# PowerSupply.net
KiCad netlist of a schematic drawn in Altium Designer
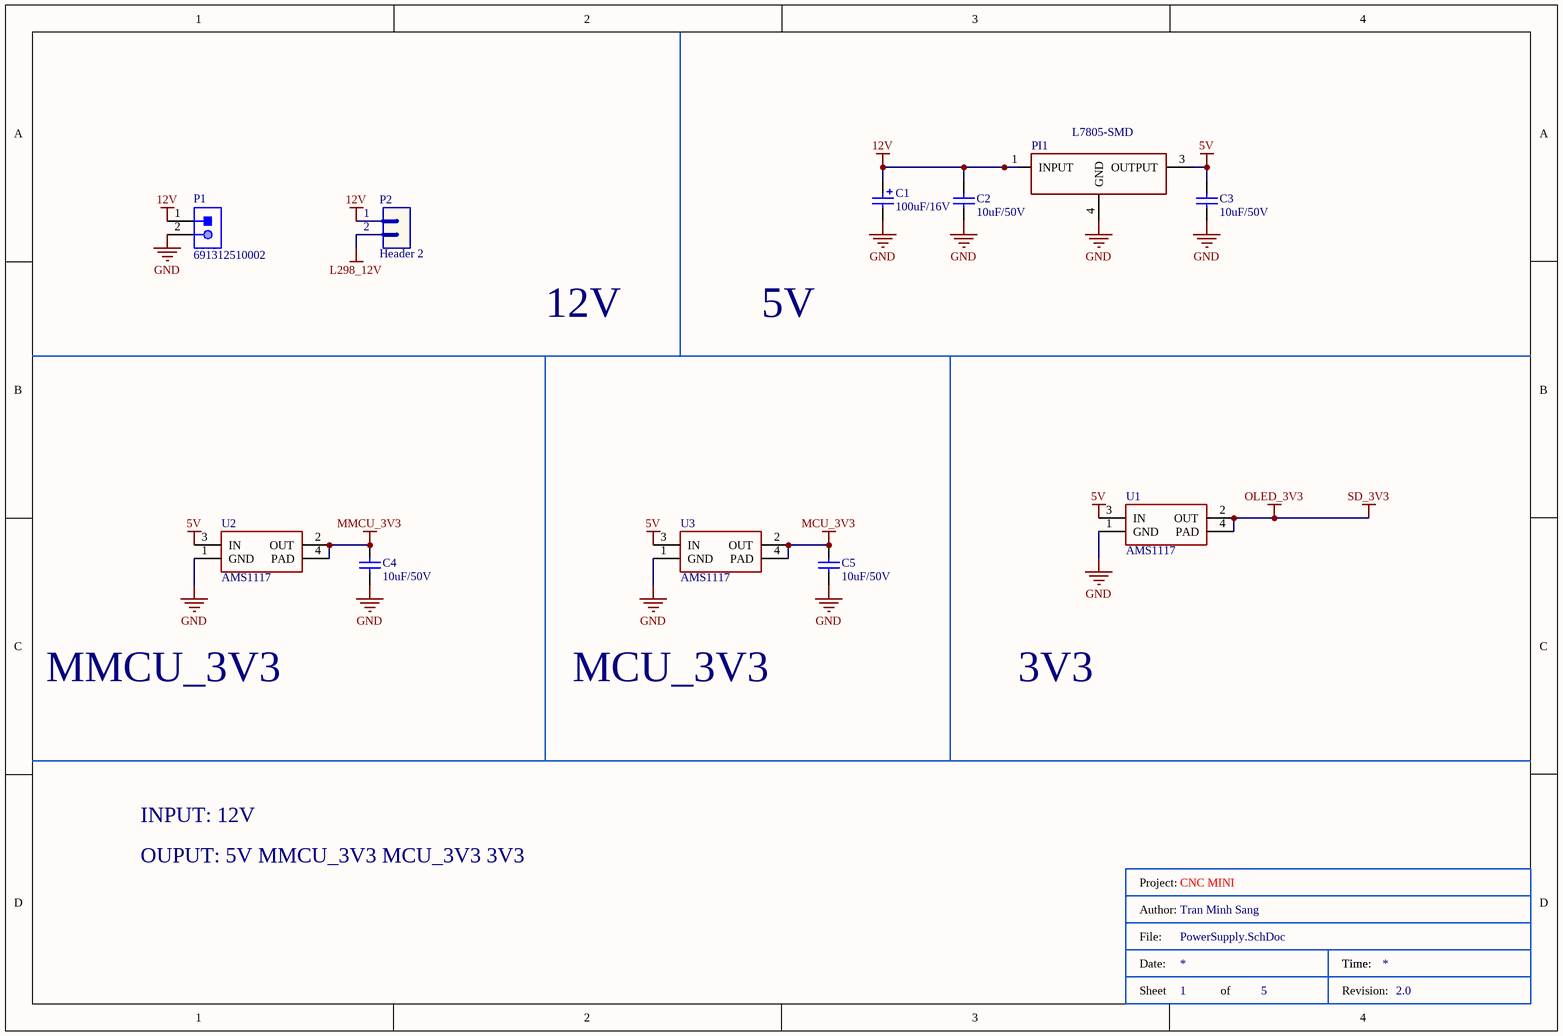
[diagram p0: PowerSupply.SchDoc]

(export (version "E")
  (design (tool "Eeschema 10.0.6"))
  (components
    (comp (ref "C1")
      (value "100uF/16V")
      (footprint "CAP-SM-AL-SIZE-D-D6L6")
      (description "CAP ALUM 100UF 20% 16V SMD")
      (fields
        (field (name "MANUFACTURER") "Nichicon")
        (field (name "MANUFACTURER PART NUMBER") "UWX1C101MCL1GB")
      )
      (libsource (lib "capacitor-smd") (part "Cap-Al-100uF-16V-D6L5"))
    )
    (comp (ref "C2")
      (value "10uF/50V")
      (footprint "CAP-SM-0805")
      (description "CAP CER 10UF 50V X5R 0805")
      (fields
        (field (name "MANUFACTURER") "Yageo")
        (field (name "MANUFACTURER PART NUMBER") "CC0805KKX5R9BB106")
      )
      (libsource (lib "capacitor-smd") (part "Cap-10uF-50V-0805"))
    )
    (comp (ref "C3")
      (value "10uF/50V")
      (footprint "CAP-SM-0805")
      (description "CAP CER 10UF 50V X5R 0805")
      (fields
        (field (name "MANUFACTURER") "Yageo")
        (field (name "MANUFACTURER PART NUMBER") "CC0805KKX5R9BB106")
      )
      (libsource (lib "capacitor-smd") (part "Cap-10uF-50V-0805"))
    )
    (comp (ref "C4")
      (value "10uF/50V")
      (footprint "CAP-SM-0805")
      (description "CAP CER 10UF 50V X5R 0805")
      (fields
        (field (name "MANUFACTURER") "Yageo")
        (field (name "MANUFACTURER PART NUMBER") "CC0805KKX5R9BB106")
      )
      (libsource (lib "capacitor-smd") (part "Cap-10uF-50V-0805"))
    )
    (comp (ref "C5")
      (value "10uF/50V")
      (footprint "CAP-SM-0805")
      (description "CAP CER 10UF 50V X5R 0805")
      (fields
        (field (name "MANUFACTURER") "Yageo")
        (field (name "MANUFACTURER PART NUMBER") "CC0805KKX5R9BB106")
      )
      (libsource (lib "capacitor-smd") (part "Cap-10uF-50V-0805"))
    )
    (comp (ref "P1")
      (value "691312510002")
      (footprint "691312510002")
      (description "WR-TBL Serie 312 Open Horizontal PCB Header, Pluggable, pitch 5.08mm, 2p")
      (fields (field (name "PUBLISHER") "Wurth Elektronik"))
      (libsource (lib "WR-TBL_Pluggable PCB Header") (part "691312510002"))
    )
    (comp (ref "P2")
      (value "Header 2")
      (footprint "JP2")
      (description "Header, 2-Pin")
      (fields (field (name "LOCAL SUPPLIER PART NUMBER") "x") (field (name "PUBLISHER") "Altium Limited"))
      (libsource (lib "header-connector") (part "Header 2"))
    )
    (comp (ref "PI1")
      (value "L7805-SMD")
      (footprint "TO254P1435X464-4N")
      (libsource (lib "PIFWRobot") (part "L7805-SMD"))
    )
    (comp (ref "U1")
      (value "AMS1117")
      (footprint "SOT223")
      (description "Available in 1.8V, 2.5V, 2.85V, 3.3V, 5V, and  Adjustable Versions")
      (libsource (lib "power-ic-module") (part "AMS1117"))
    )
    (comp (ref "U2")
      (value "AMS1117")
      (footprint "SOT223")
      (description "Available in 1.8V, 2.5V, 2.85V, 3.3V, 5V, and  Adjustable Versions")
      (libsource (lib "power-ic-module") (part "AMS1117"))
    )
    (comp (ref "U3")
      (value "AMS1117")
      (footprint "SOT223")
      (description "Available in 1.8V, 2.5V, 2.85V, 3.3V, 5V, and  Adjustable Versions")
      (libsource (lib "power-ic-module") (part "AMS1117"))
    )
  )
  (nets
    (net (code "1") (name "5V") (class "Default")
      (node (ref "C3") (pin "2") (pinfunction "2_2") (pintype "passive"))
      (node (ref "PI1") (pin "3") (pinfunction "OUTPUT_3") (pintype "passive"))
      (node (ref "U1") (pin "3") (pinfunction "IN_3") (pintype "passive"))
      (node (ref "U2") (pin "3") (pinfunction "IN_3") (pintype "passive"))
      (node (ref "U3") (pin "3") (pinfunction "IN_3") (pintype "passive"))
    )
    (net (code "2") (name "12V") (class "Default")
      (node (ref "C1") (pin "1") (pinfunction "1_1") (pintype "passive"))
      (node (ref "C2") (pin "2") (pinfunction "2_2") (pintype "passive"))
      (node (ref "P1") (pin "1") (pinfunction "1_1") (pintype "passive"))
      (node (ref "P2") (pin "1") (pinfunction "1_1") (pintype "passive"))
      (node (ref "PI1") (pin "1") (pinfunction "INPUT_1") (pintype "passive"))
    )
    (net (code "3") (name "GND") (class "Default")
      (node (ref "C1") (pin "2") (pinfunction "2_2") (pintype "passive"))
      (node (ref "C2") (pin "1") (pinfunction "1_1") (pintype "passive"))
      (node (ref "C3") (pin "1") (pinfunction "1_1") (pintype "passive"))
      (node (ref "C4") (pin "2") (pinfunction "2_2") (pintype "passive"))
      (node (ref "C5") (pin "2") (pinfunction "2_2") (pintype "passive"))
      (node (ref "P1") (pin "2") (pinfunction "2_2") (pintype "passive"))
      (node (ref "PI1") (pin "4") (pinfunction "GND_4") (pintype "passive"))
      (node (ref "U1") (pin "1") (pinfunction "GND_1") (pintype "passive"))
      (node (ref "U2") (pin "1") (pinfunction "GND_1") (pintype "passive"))
      (node (ref "U3") (pin "1") (pinfunction "GND_1") (pintype "passive"))
    )
    (net (code "4") (name "L298_12V") (class "Default")
      (node (ref "P2") (pin "2") (pinfunction "2_2") (pintype "passive"))
    )
    (net (code "5") (name "MCU_3V3") (class "Default")
      (node (ref "C5") (pin "1") (pinfunction "1_1") (pintype "passive"))
      (node (ref "U3") (pin "2") (pinfunction "OUT_2") (pintype "passive"))
      (node (ref "U3") (pin "4") (pinfunction "PAD_4") (pintype "passive"))
    )
    (net (code "6") (name "MMCU_3V3") (class "Default")
      (node (ref "C4") (pin "1") (pinfunction "1_1") (pintype "passive"))
      (node (ref "U2") (pin "2") (pinfunction "OUT_2") (pintype "passive"))
      (node (ref "U2") (pin "4") (pinfunction "PAD_4") (pintype "passive"))
    )
    (net (code "7") (name "OLED_3V3") (class "Default")
      (node (ref "U1") (pin "2") (pinfunction "OUT_2") (pintype "passive"))
      (node (ref "U1") (pin "4") (pinfunction "PAD_4") (pintype "passive"))
    )
  )
)
